# MCU-BLE.net
KiCad netlist of a schematic drawn in Altium Designer
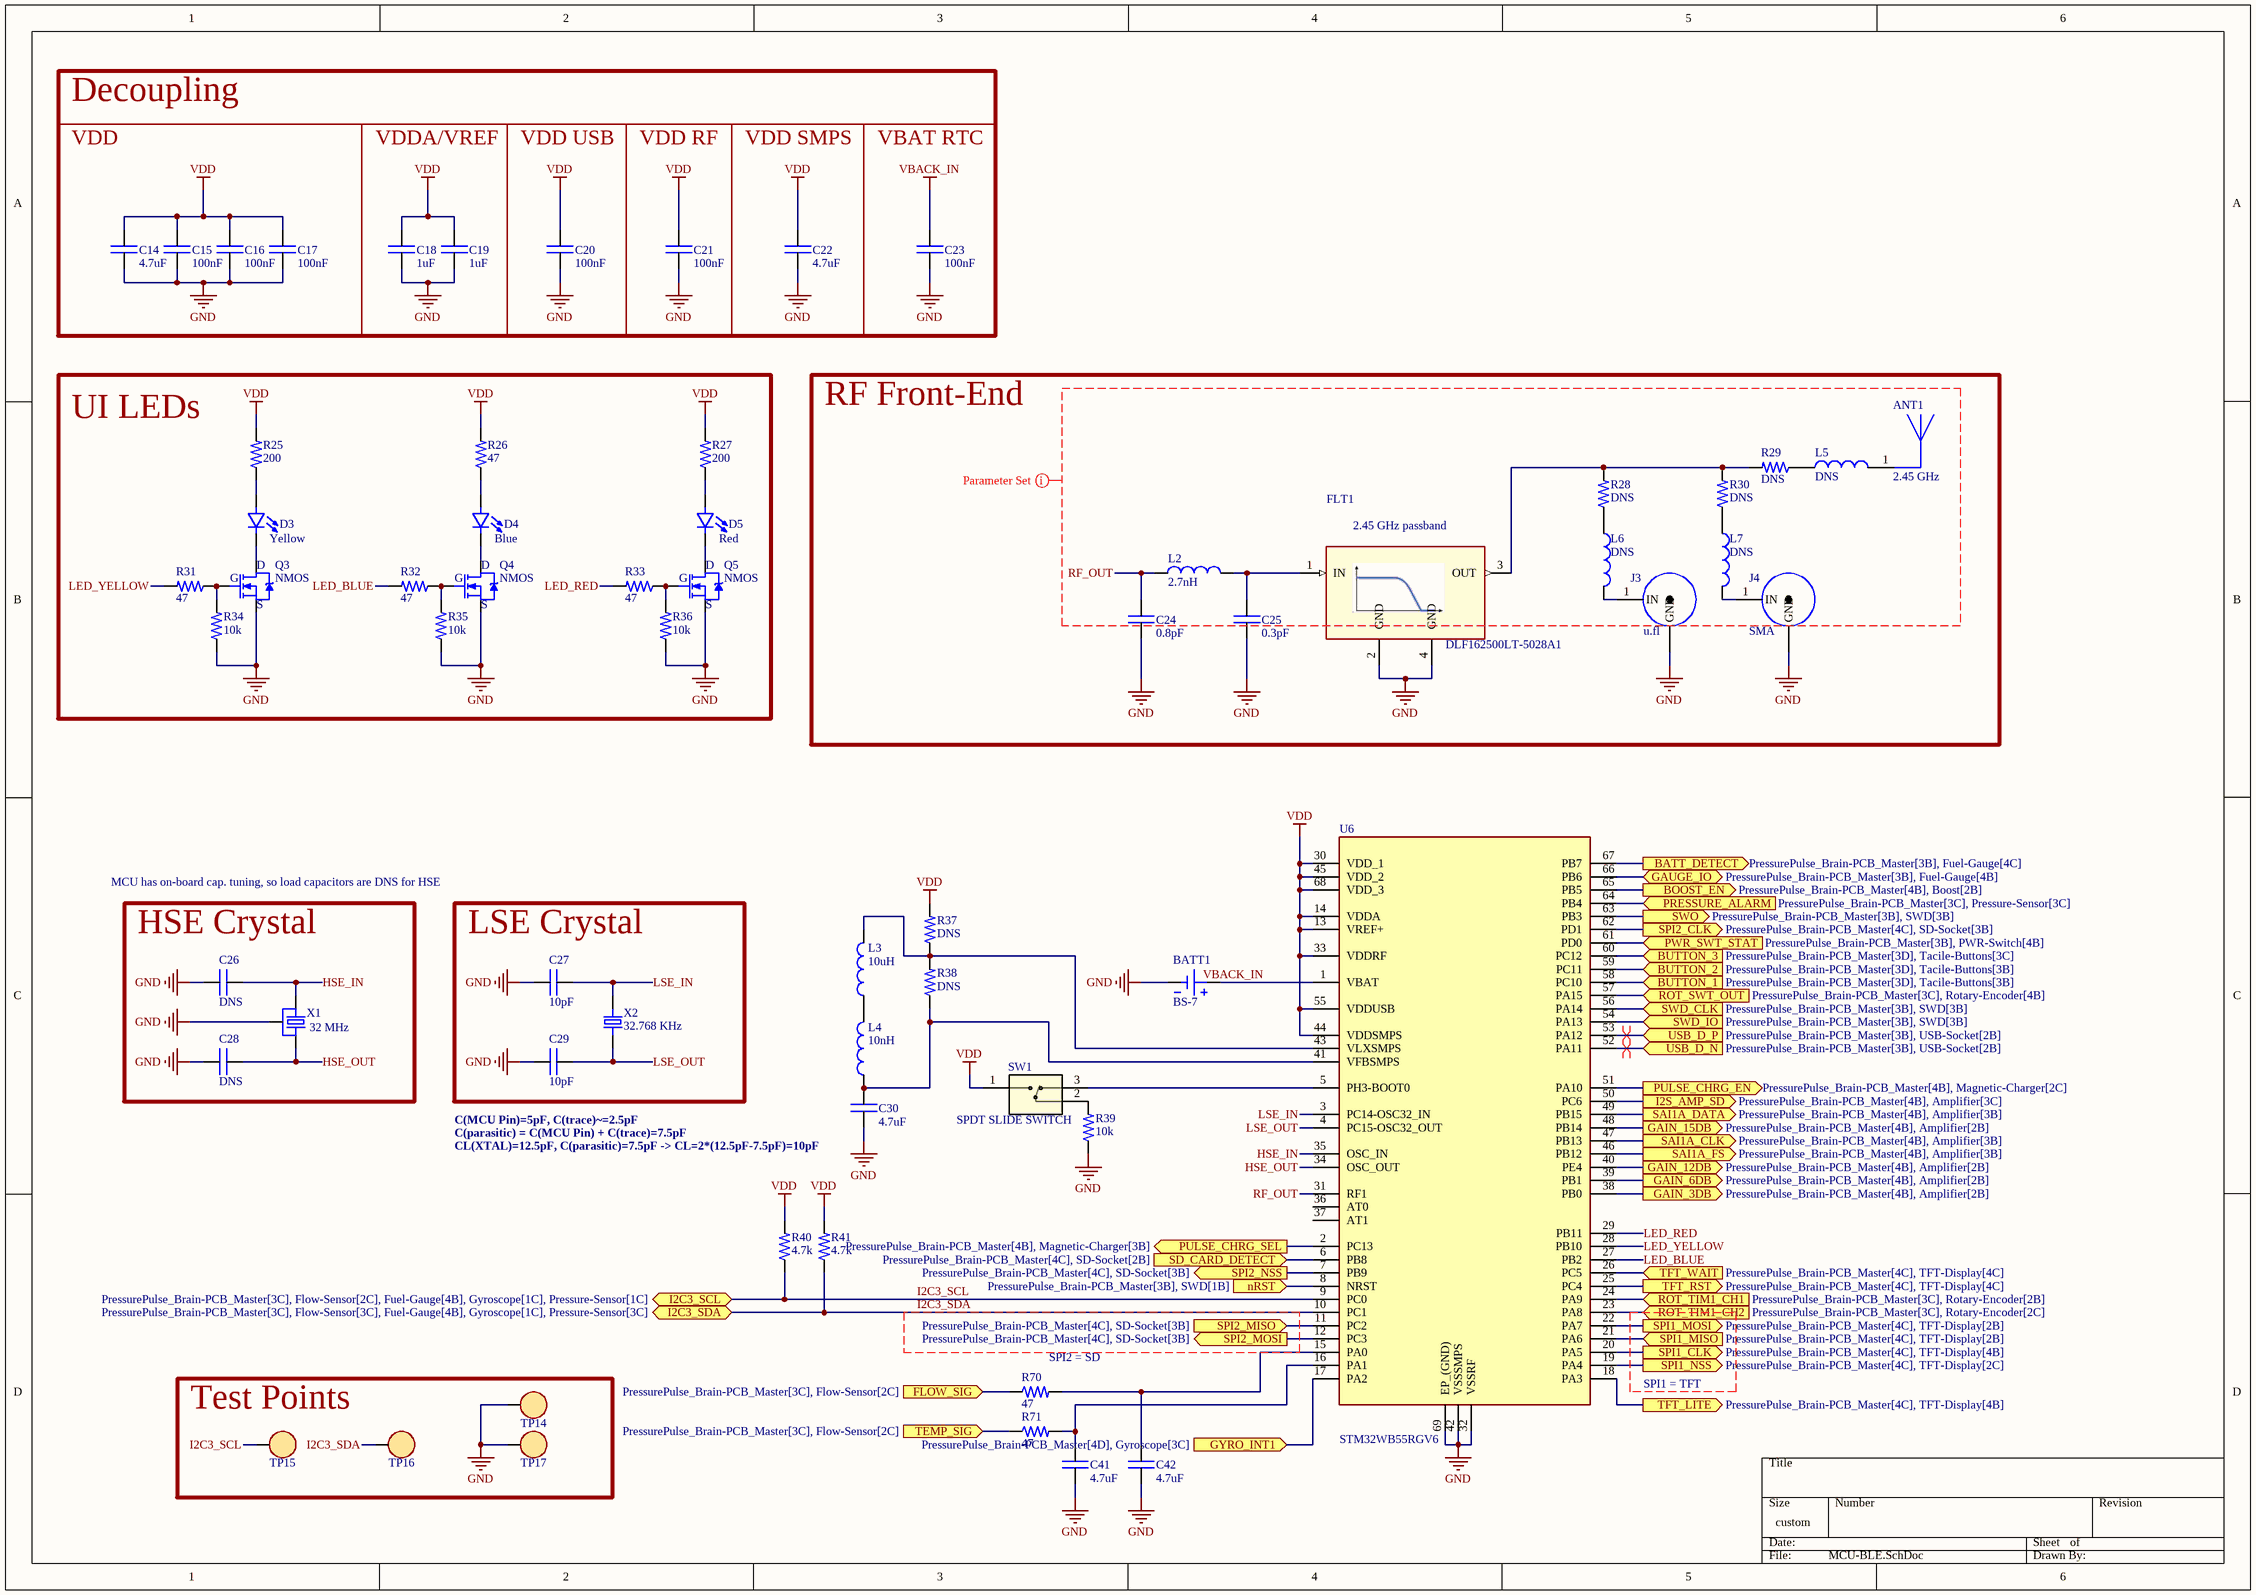
[diagram p0: MCU-BLE.SchDoc]

(export (version "E")
  (design (tool "Eeschema 10.0.6"))
  (components
    (comp (ref "ANT1")
      (value "CHIP ANTENNA")
      (footprint "PressurePulse:ANT_ANT7020LL05R0870A_PUL-L")
      (fields (field (name "MFR") "Pulse Electronics") (field (name "CENTER FREQUENCY") "2.45 GHz"))
      (libsource (lib "PressurePulse") (part "CHIP ANTENNA"))
    )
    (comp (ref "BATT1")
      (value "BS-7")
      (footprint "PressurePulse:BAT_BS-7")
      (description "Battery Holder (Open) Coin, 20.0mm 1 Cell PC Pin")
      (fields (field (name "MP") "BS-2-1") (field (name "MF") "Q&J"))
      (libsource (lib "PressurePulse") (part "COIN CELL BATT"))
    )
    (comp (ref "C14")
      (value "4.7uF")
      (footprint "PressurePulse:0402C")
      (description "Capaicitor")
      (fields (field (name "Comment") "CAP"))
      (libsource (lib "PressurePulse") (part "CAP"))
    )
    (comp (ref "C15")
      (value "100nF")
      (footprint "PressurePulse:0402C")
      (description "Capaicitor")
      (fields (field (name "Comment") "CAP"))
      (libsource (lib "PressurePulse") (part "CAP"))
    )
    (comp (ref "C16")
      (value "100nF")
      (footprint "PressurePulse:0402C")
      (description "Capaicitor")
      (fields (field (name "Comment") "CAP"))
      (libsource (lib "PressurePulse") (part "CAP"))
    )
    (comp (ref "C17")
      (value "100nF")
      (footprint "PressurePulse:0402C")
      (description "Capaicitor")
      (fields (field (name "Comment") "CAP"))
      (libsource (lib "PressurePulse") (part "CAP"))
    )
    (comp (ref "C18")
      (value "1uF")
      (footprint "PressurePulse:0402C")
      (description "Capaicitor")
      (fields (field (name "Comment") "CAP"))
      (libsource (lib "PressurePulse") (part "CAP"))
    )
    (comp (ref "C19")
      (value "1uF")
      (footprint "PressurePulse:0402C")
      (description "Capaicitor")
      (fields (field (name "Comment") "CAP"))
      (libsource (lib "PressurePulse") (part "CAP"))
    )
    (comp (ref "C20")
      (value "100nF")
      (footprint "PressurePulse:0402C")
      (description "Capaicitor")
      (fields (field (name "Comment") "CAP"))
      (libsource (lib "PressurePulse") (part "CAP"))
    )
    (comp (ref "C21")
      (value "100nF")
      (footprint "PressurePulse:0402C")
      (description "Capaicitor")
      (fields (field (name "Comment") "CAP"))
      (libsource (lib "PressurePulse") (part "CAP"))
    )
    (comp (ref "C22")
      (value "4.7uF")
      (footprint "PressurePulse:0402C")
      (description "Capaicitor")
      (fields (field (name "Comment") "CAP"))
      (libsource (lib "PressurePulse") (part "CAP"))
    )
    (comp (ref "C23")
      (value "100nF")
      (footprint "PressurePulse:0402C")
      (description "Capaicitor")
      (fields (field (name "Comment") "CAP"))
      (libsource (lib "PressurePulse") (part "CAP"))
    )
    (comp (ref "C24")
      (value "0.8pF")
      (footprint "PressurePulse:0603C")
      (description "Capacitor")
      (fields (field (name "Comment") "CAP"))
      (libsource (lib "PressurePulse") (part "CAP"))
    )
    (comp (ref "C25")
      (value "0.3pF")
      (footprint "PressurePulse:0402C")
      (description "Capacitor")
      (fields (field (name "Comment") "CAP"))
      (libsource (lib "PressurePulse") (part "CAP"))
    )
    (comp (ref "C26")
      (value "DNS")
      (footprint "PressurePulse:0402C")
      (description "Capaicitor")
      (fields (field (name "Comment") "CAP"))
      (libsource (lib "PressurePulse") (part "CAP"))
    )
    (comp (ref "C27")
      (value "10pF")
      (footprint "PressurePulse:0402C")
      (description "Capaicitor")
      (fields (field (name "Comment") "CAP"))
      (libsource (lib "PressurePulse") (part "CAP"))
    )
    (comp (ref "C28")
      (value "DNS")
      (footprint "PressurePulse:0402C")
      (description "Capaicitor")
      (fields (field (name "Comment") "CAP"))
      (libsource (lib "PressurePulse") (part "CAP"))
    )
    (comp (ref "C29")
      (value "10pF")
      (footprint "PressurePulse:0402C")
      (description "Capaicitor")
      (fields (field (name "Comment") "CAP"))
      (libsource (lib "PressurePulse") (part "CAP"))
    )
    (comp (ref "C30")
      (value "4.7uF")
      (footprint "PressurePulse:0402C")
      (description "Capaicitor")
      (fields (field (name "Comment") "CAP"))
      (libsource (lib "PressurePulse") (part "CAP"))
    )
    (comp (ref "C41")
      (value "4.7uF")
      (footprint "PressurePulse:0402C")
      (description "Capacitor")
      (fields (field (name "Comment") "CAP"))
      (libsource (lib "PressurePulse") (part "CAP"))
    )
    (comp (ref "C42")
      (value "4.7uF")
      (footprint "PressurePulse:0402C")
      (description "Capacitor")
      (fields (field (name "Comment") "CAP"))
      (libsource (lib "PressurePulse") (part "CAP"))
    )
    (comp (ref "D3")
      (value "LED - single")
      (footprint "PressurePulse:0603-LED")
      (description "LED")
      (fields (field (name "COLOR") "Yellow"))
      (libsource (lib "PressurePulse") (part "LED - single"))
    )
    (comp (ref "D4")
      (value "LED - single")
      (footprint "PressurePulse:0603-LED")
      (description "LED")
      (fields (field (name "COLOR") "Blue"))
      (libsource (lib "PressurePulse") (part "LED - single"))
    )
    (comp (ref "D5")
      (value "LED - single")
      (footprint "PressurePulse:0603-LED")
      (description "LED")
      (fields (field (name "COLOR") "Red"))
      (libsource (lib "PressurePulse") (part "LED - single"))
    )
    (comp (ref "FLT1")
      (value "DLF162500LT-5028A1")
      (footprint "PressurePulse:DLF-4_1P6X0P8")
      (description "RF FILTER LOW PASS 2.45GHZ 0603")
      (fields (field (name "MFR") "TDK"))
      (libsource (lib "PressurePulse") (part "2.45GHz LPF"))
    )
    (comp (ref "J3")
      (value "u.fl")
      (footprint "PressurePulse:U.FL")
      (description "u.fl 50Ohm")
      (fields (field (name "MFR") "HRS(Hirose)"))
      (libsource (lib "PressurePulse") (part "u.fl CONN"))
    )
    (comp (ref "J4")
      (value "SMA")
      (footprint "PressurePulse:SMA TH RA")
      (description "SMA 50Ohm")
      (fields (field (name "MFR") "DreamLNK"))
      (libsource (lib "PressurePulse") (part "SMA"))
    )
    (comp (ref "L2")
      (value "2.7nH")
      (footprint "PressurePulse:0402L")
      (description "INDUCTOR")
      (fields (field (name "Comment") "IND"))
      (libsource (lib "PressurePulse") (part "IND"))
    )
    (comp (ref "L3")
      (value "10uH")
      (footprint "PressurePulse:0805L")
      (description "INDUCTOR")
      (fields (field (name "Comment") "IND"))
      (libsource (lib "PressurePulse") (part "IND"))
    )
    (comp (ref "L4")
      (value "10nH")
      (footprint "PressurePulse:0402L")
      (description "INDUCTOR")
      (fields (field (name "Comment") "IND"))
      (libsource (lib "PressurePulse") (part "IND"))
    )
    (comp (ref "L5")
      (value "DNS")
      (footprint "PressurePulse:0402L")
      (description "INDUCTOR")
      (fields (field (name "Comment") "IND"))
      (libsource (lib "PressurePulse") (part "IND"))
    )
    (comp (ref "L6")
      (value "DNS")
      (footprint "PressurePulse:0402L")
      (description "INDUCTOR")
      (fields (field (name "Comment") "IND"))
      (libsource (lib "PressurePulse") (part "IND"))
    )
    (comp (ref "L7")
      (value "DNS")
      (footprint "PressurePulse:0402L")
      (description "INDUCTOR")
      (fields (field (name "Comment") "IND"))
      (libsource (lib "PressurePulse") (part "IND"))
    )
    (comp (ref "Q3")
      (value "NMOS")
      (footprint "PressurePulse:SOT-23")
      (description "100V 1.6A 1.3W 220mΩ@10V,1.6A N Channel SOT-23  MOSFETs ROHS")
      (fields (field (name "MFR") "Infineon"))
      (libsource (lib "PressurePulse") (part "NMOS"))
    )
    (comp (ref "Q4")
      (value "NMOS")
      (footprint "PressurePulse:SOT-23")
      (description "100V 1.6A 1.3W 220mΩ@10V,1.6A N Channel SOT-23  MOSFETs ROHS")
      (fields (field (name "MFR") "Infineon"))
      (libsource (lib "PressurePulse") (part "NMOS"))
    )
    (comp (ref "Q5")
      (value "NMOS")
      (footprint "PressurePulse:SOT-23")
      (description "100V 1.6A 1.3W 220mΩ@10V,1.6A N Channel SOT-23  MOSFETs ROHS")
      (fields (field (name "MFR") "Infineon"))
      (libsource (lib "PressurePulse") (part "NMOS"))
    )
    (comp (ref "R25")
      (value "200")
      (footprint "PressurePulse:0402R")
      (description "Resistor")
      (fields (field (name "Comment") "RES"))
      (libsource (lib "PressurePulse") (part "RES"))
    )
    (comp (ref "R26")
      (value "47")
      (footprint "PressurePulse:0402R")
      (description "Resistor")
      (fields (field (name "Comment") "RES"))
      (libsource (lib "PressurePulse") (part "RES"))
    )
    (comp (ref "R27")
      (value "200")
      (footprint "PressurePulse:0402R")
      (description "Resistor")
      (fields (field (name "Comment") "RES"))
      (libsource (lib "PressurePulse") (part "RES"))
    )
    (comp (ref "R28")
      (value "DNS")
      (footprint "PressurePulse:0402R")
      (description "Resistor")
      (fields (field (name "Comment") "RES"))
      (libsource (lib "PressurePulse") (part "RES"))
    )
    (comp (ref "R29")
      (value "DNS")
      (footprint "PressurePulse:0402R")
      (description "Resistor")
      (fields (field (name "Comment") "RES"))
      (libsource (lib "PressurePulse") (part "RES"))
    )
    (comp (ref "R30")
      (value "DNS")
      (footprint "PressurePulse:0402R")
      (description "Resistor")
      (fields (field (name "Comment") "RES"))
      (libsource (lib "PressurePulse") (part "RES"))
    )
    (comp (ref "R31")
      (value "47")
      (footprint "PressurePulse:0402R")
      (description "Resistor")
      (fields (field (name "Comment") "RES"))
      (libsource (lib "PressurePulse") (part "RES"))
    )
    (comp (ref "R32")
      (value "47")
      (footprint "PressurePulse:0402R")
      (description "Resistor")
      (fields (field (name "Comment") "RES"))
      (libsource (lib "PressurePulse") (part "RES"))
    )
    (comp (ref "R33")
      (value "47")
      (footprint "PressurePulse:0402R")
      (description "Resistor")
      (fields (field (name "Comment") "RES"))
      (libsource (lib "PressurePulse") (part "RES"))
    )
    (comp (ref "R34")
      (value "10k")
      (footprint "PressurePulse:0402R")
      (description "Resistor")
      (fields (field (name "Comment") "RES"))
      (libsource (lib "PressurePulse") (part "RES"))
    )
    (comp (ref "R35")
      (value "10k")
      (footprint "PressurePulse:0402R")
      (description "Resistor")
      (fields (field (name "Comment") "RES"))
      (libsource (lib "PressurePulse") (part "RES"))
    )
    (comp (ref "R36")
      (value "10k")
      (footprint "PressurePulse:0402R")
      (description "Resistor")
      (fields (field (name "Comment") "RES"))
      (libsource (lib "PressurePulse") (part "RES"))
    )
    (comp (ref "R37")
      (value "DNS")
      (footprint "PressurePulse:0402R")
      (description "Resistor")
      (fields (field (name "Comment") "RES"))
      (libsource (lib "PressurePulse") (part "RES"))
    )
    (comp (ref "R38")
      (value "DNS")
      (footprint "PressurePulse:0402R")
      (description "Resistor")
      (fields (field (name "Comment") "RES"))
      (libsource (lib "PressurePulse") (part "RES"))
    )
    (comp (ref "R39")
      (value "10k")
      (footprint "PressurePulse:0402R")
      (description "Resistor")
      (fields (field (name "Comment") "RES"))
      (libsource (lib "PressurePulse") (part "RES"))
    )
    (comp (ref "R40")
      (value "4.7k")
      (footprint "PressurePulse:0402R")
      (description "Resistor")
      (fields (field (name "Comment") "RES"))
      (libsource (lib "PressurePulse") (part "RES"))
    )
    (comp (ref "R41")
      (value "4.7k")
      (footprint "PressurePulse:0402R")
      (description "Resistor")
      (fields (field (name "Comment") "RES"))
      (libsource (lib "PressurePulse") (part "RES"))
    )
    (comp (ref "R70")
      (value "47")
      (footprint "PressurePulse:0402R")
      (description "Resistor")
      (fields (field (name "Comment") "RES"))
      (libsource (lib "PressurePulse") (part "RES"))
    )
    (comp (ref "R71")
      (value "47")
      (footprint "PressurePulse:0402R")
      (description "Resistor")
      (fields (field (name "Comment") "RES"))
      (libsource (lib "PressurePulse") (part "RES"))
    )
    (comp (ref "SW1")
      (value "SPDT SLIDE SWITCH")
      (footprint "PressurePulse:JS102011SCQN")
      (fields (field (name "MFR") "C&K"))
      (libsource (lib "PressurePulse") (part "SPDT SLIDE SWITCH"))
    )
    (comp (ref "TP14")
      (value "RH-5019")
      (footprint "PressurePulse:TP - RH-5019")
      (fields (field (name "MFR") "ronghe"))
      (libsource (lib "PressurePulse") (part "TEST POINT"))
    )
    (comp (ref "TP15")
      (value "RH-5019")
      (footprint "PressurePulse:TP - RH-5019")
      (fields (field (name "MFR") "ronghe"))
      (libsource (lib "PressurePulse") (part "TEST POINT"))
    )
    (comp (ref "TP16")
      (value "RH-5019")
      (footprint "PressurePulse:TP - RH-5019")
      (fields (field (name "MFR") "ronghe"))
      (libsource (lib "PressurePulse") (part "TEST POINT"))
    )
    (comp (ref "TP17")
      (value "RH-5019")
      (footprint "PressurePulse:TP - RH-5019")
      (fields (field (name "MFR") "ronghe"))
      (libsource (lib "PressurePulse") (part "TEST POINT"))
    )
    (comp (ref "U6")
      (value "STM32WB55RGV6")
      (footprint "PressurePulse:VQFN-68")
      (fields (field (name "MFR") "STMicroelectronics"))
      (libsource (lib "PressurePulse") (part "STM32WB55RGV6"))
    )
    (comp (ref "X1")
      (value "XTAL-OSC_32MHz")
      (footprint "PressurePulse:32MHZ_SMD1612-4P")
      (description "SMD Tuning Fork Crystal")
      (fields (field (name "FREQUENCY") "32 MHz"))
      (libsource (lib "PressurePulse") (part "XTAL-OSC_32MHz"))
    )
    (comp (ref "X2")
      (value "XTAL-OSC_32.768kHz")
      (footprint "PressurePulse:XTAL_ECS-.327-12.5-34B-TR")
      (description "32.768kHz 12.5pF ±20ppm SMD3215-2P  Crystals ROHS")
      (fields (field (name "MFR") "CITIZEN") (field (name "FREQUENCY") "32.768 KHz"))
      (libsource (lib "PressurePulse") (part "XTAL-OSC_32.768kHz"))
    )
  )
  (nets
    (net (code "1") (name "/BATT_DETECT") (class "Default")
      (node (ref "U6") (pin "67") (pinfunction "PB7_67") (pintype "passive"))
    )
    (net (code "2") (name "/BOOST_EN") (class "Default")
      (node (ref "U6") (pin "65") (pinfunction "PB5_65") (pintype "passive"))
    )
    (net (code "3") (name "/BUTTON_1") (class "Default")
      (node (ref "U6") (pin "58") (pinfunction "PC10_58") (pintype "passive"))
    )
    (net (code "4") (name "/BUTTON_2") (class "Default")
      (node (ref "U6") (pin "59") (pinfunction "PC11_59") (pintype "passive"))
    )
    (net (code "5") (name "/BUTTON_3") (class "Default")
      (node (ref "U6") (pin "60") (pinfunction "PC12_60") (pintype "passive"))
    )
    (net (code "6") (name "/FLOW_SIG") (class "Default")
      (node (ref "R70") (pin "1") (pinfunction "1_1") (pintype "passive"))
    )
    (net (code "7") (name "/GAIN_3DB") (class "Default")
      (node (ref "U6") (pin "38") (pinfunction "PB0_38") (pintype "passive"))
    )
    (net (code "8") (name "/GAIN_6DB") (class "Default")
      (node (ref "U6") (pin "39") (pinfunction "PB1_39") (pintype "passive"))
    )
    (net (code "9") (name "/GAIN_12DB") (class "Default")
      (node (ref "U6") (pin "40") (pinfunction "PE4_40") (pintype "passive"))
    )
    (net (code "10") (name "/GAIN_15DB") (class "Default")
      (node (ref "U6") (pin "48") (pinfunction "PB14_48") (pintype "passive"))
    )
    (net (code "11") (name "/GAUGE_IO") (class "Default")
      (node (ref "U6") (pin "66") (pinfunction "PB6_66") (pintype "passive"))
    )
    (net (code "12") (name "/GYRO_INT1") (class "Default")
      (node (ref "U6") (pin "17") (pinfunction "PA2_17") (pintype "passive"))
    )
    (net (code "13") (name "/HSE_IN") (class "Default")
      (node (ref "C26") (pin "1") (pinfunction "1_1") (pintype "passive"))
      (node (ref "U6") (pin "35") (pinfunction "OSC_IN_35") (pintype "passive"))
      (node (ref "X1") (pin "1") (pinfunction "1_1") (pintype "passive"))
    )
    (net (code "14") (name "/HSE_OUT") (class "Default")
      (node (ref "C28") (pin "1") (pinfunction "1_1") (pintype "passive"))
      (node (ref "U6") (pin "34") (pinfunction "OSC_OUT_34") (pintype "passive"))
      (node (ref "X1") (pin "3") (pinfunction "3_3") (pintype "passive"))
    )
    (net (code "15") (name "/I2C3_SCL") (class "Default")
      (node (ref "R40") (pin "1") (pinfunction "1_1") (pintype "passive"))
      (node (ref "TP15") (pin "1") (pinfunction "1_1") (pintype "passive"))
      (node (ref "U6") (pin "9") (pinfunction "PC0_9") (pintype "passive"))
    )
    (net (code "16") (name "/I2C3_SDA") (class "Default")
      (node (ref "R41") (pin "1") (pinfunction "1_1") (pintype "passive"))
      (node (ref "TP16") (pin "1") (pinfunction "1_1") (pintype "passive"))
      (node (ref "U6") (pin "10") (pinfunction "PC1_10") (pintype "passive"))
    )
    (net (code "17") (name "/I2S_AMP_SD") (class "Default")
      (node (ref "U6") (pin "50") (pinfunction "PC6_50") (pintype "passive"))
    )
    (net (code "18") (name "/LED_BLUE") (class "Default")
      (node (ref "R32") (pin "2") (pinfunction "2_2") (pintype "passive"))
      (node (ref "U6") (pin "27") (pinfunction "PB2_27") (pintype "passive"))
    )
    (net (code "19") (name "/LED_RED") (class "Default")
      (node (ref "R33") (pin "2") (pinfunction "2_2") (pintype "passive"))
      (node (ref "U6") (pin "29") (pinfunction "PB11_29") (pintype "passive"))
    )
    (net (code "20") (name "/LED_YELLOW") (class "Default")
      (node (ref "R31") (pin "2") (pinfunction "2_2") (pintype "passive"))
      (node (ref "U6") (pin "28") (pinfunction "PB10_28") (pintype "passive"))
    )
    (net (code "21") (name "/LSE_IN") (class "Default")
      (node (ref "C27") (pin "1") (pinfunction "1_1") (pintype "passive"))
      (node (ref "U6") (pin "3") (pinfunction "PC14-OSC32_IN_3") (pintype "passive"))
      (node (ref "X2") (pin "2") (pinfunction "2_2") (pintype "passive"))
    )
    (net (code "22") (name "/LSE_OUT") (class "Default")
      (node (ref "C29") (pin "1") (pinfunction "1_1") (pintype "passive"))
      (node (ref "U6") (pin "4") (pinfunction "PC15-OSC32_OUT_4") (pintype "passive"))
      (node (ref "X2") (pin "1") (pinfunction "1_1") (pintype "passive"))
    )
    (net (code "23") (name "/PRESSURE_ALARM") (class "Default")
      (node (ref "U6") (pin "64") (pinfunction "PB4_64") (pintype "passive"))
    )
    (net (code "24") (name "/PULSE_CHRG_EN") (class "Default")
      (node (ref "U6") (pin "51") (pinfunction "PA10_51") (pintype "passive"))
    )
    (net (code "25") (name "/PULSE_CHRG_SEL") (class "Default")
      (node (ref "U6") (pin "2") (pinfunction "PC13_2") (pintype "passive"))
    )
    (net (code "26") (name "/PWR_SWT_STAT") (class "Default")
      (node (ref "U6") (pin "61") (pinfunction "PD0_61") (pintype "passive"))
    )
    (net (code "27") (name "/RF_OUT") (class "Default")
      (node (ref "C24") (pin "2") (pinfunction "2_2") (pintype "passive"))
      (node (ref "L2") (pin "1") (pinfunction "1_1") (pintype "passive"))
      (node (ref "U6") (pin "31") (pinfunction "RF1_31") (pintype "passive"))
    )
    (net (code "28") (name "/ROT_SWT_OUT") (class "Default")
      (node (ref "U6") (pin "57") (pinfunction "PA15_57") (pintype "passive"))
    )
    (net (code "29") (name "/ROT_TIM1_CH1") (class "Default")
      (node (ref "U6") (pin "24") (pinfunction "PA9_24") (pintype "passive"))
    )
    (net (code "30") (name "/ROT_TIM1_CH2") (class "Default")
      (node (ref "U6") (pin "23") (pinfunction "PA8_23") (pintype "passive"))
    )
    (net (code "31") (name "/SAI1A_CLK") (class "Default")
      (node (ref "U6") (pin "47") (pinfunction "PB13_47") (pintype "passive"))
    )
    (net (code "32") (name "/SAI1A_DATA") (class "Default")
      (node (ref "U6") (pin "49") (pinfunction "PB15_49") (pintype "passive"))
    )
    (net (code "33") (name "/SAI1A_FS") (class "Default")
      (node (ref "U6") (pin "46") (pinfunction "PB12_46") (pintype "passive"))
    )
    (net (code "34") (name "/SD_CARD_DETECT") (class "Default")
      (node (ref "U6") (pin "6") (pinfunction "PB8_6") (pintype "passive"))
    )
    (net (code "35") (name "/SPI1_CLK") (class "Default")
      (node (ref "U6") (pin "20") (pinfunction "PA5_20") (pintype "passive"))
    )
    (net (code "36") (name "/SPI1_MISO") (class "Default")
      (node (ref "U6") (pin "21") (pinfunction "PA6_21") (pintype "passive"))
    )
    (net (code "37") (name "/SPI1_MOSI") (class "Default")
      (node (ref "U6") (pin "22") (pinfunction "PA7_22") (pintype "passive"))
    )
    (net (code "38") (name "/SPI1_NSS") (class "Default")
      (node (ref "U6") (pin "19") (pinfunction "PA4_19") (pintype "passive"))
    )
    (net (code "39") (name "/SPI2_CLK") (class "Default")
      (node (ref "U6") (pin "62") (pinfunction "PD1_62") (pintype "passive"))
    )
    (net (code "40") (name "/SPI2_MISO") (class "Default")
      (node (ref "U6") (pin "11") (pinfunction "PC2_11") (pintype "passive"))
    )
    (net (code "41") (name "/SPI2_MOSI") (class "Default")
      (node (ref "U6") (pin "12") (pinfunction "PC3_12") (pintype "passive"))
    )
    (net (code "42") (name "/SPI2_NSS") (class "Default")
      (node (ref "U6") (pin "7") (pinfunction "PB9_7") (pintype "passive"))
    )
    (net (code "43") (name "/SWD_CLK") (class "Default")
      (node (ref "U6") (pin "56") (pinfunction "PA14_56") (pintype "passive"))
    )
    (net (code "44") (name "/SWD_IO") (class "Default")
      (node (ref "U6") (pin "54") (pinfunction "PA13_54") (pintype "passive"))
    )
    (net (code "45") (name "/SWO") (class "Default")
      (node (ref "U6") (pin "63") (pinfunction "PB3_63") (pintype "passive"))
    )
    (net (code "46") (name "/TEMP_SIG") (class "Default")
      (node (ref "R71") (pin "1") (pinfunction "1_1") (pintype "passive"))
    )
    (net (code "47") (name "/TFT_LITE") (class "Default")
      (node (ref "U6") (pin "18") (pinfunction "PA3_18") (pintype "passive"))
    )
    (net (code "48") (name "/TFT_RST") (class "Default")
      (node (ref "U6") (pin "25") (pinfunction "PC4_25") (pintype "passive"))
    )
    (net (code "49") (name "/TFT_WAIT") (class "Default")
      (node (ref "U6") (pin "26") (pinfunction "PC5_26") (pintype "passive"))
    )
    (net (code "50") (name "/USB_D_N") (class "Default")
      (node (ref "U6") (pin "52") (pinfunction "PA11_52") (pintype "passive"))
    )
    (net (code "51") (name "/USB_D_P") (class "Default")
      (node (ref "U6") (pin "53") (pinfunction "PA12_53") (pintype "passive"))
    )
    (net (code "52") (name "/nRST") (class "Default")
      (node (ref "U6") (pin "8") (pinfunction "NRST_8") (pintype "passive"))
    )
    (net (code "53") (name "GND") (class "Default")
      (node (ref "BATT1") (pin "2") (pinfunction "NEG_2") (pintype "passive"))
      (node (ref "C14") (pin "1") (pinfunction "1_1") (pintype "passive"))
      (node (ref "C15") (pin "1") (pinfunction "1_1") (pintype "passive"))
      (node (ref "C16") (pin "1") (pinfunction "1_1") (pintype "passive"))
      (node (ref "C17") (pin "1") (pinfunction "1_1") (pintype "passive"))
      (node (ref "C18") (pin "1") (pinfunction "1_1") (pintype "passive"))
      (node (ref "C19") (pin "1") (pinfunction "1_1") (pintype "passive"))
      (node (ref "C20") (pin "1") (pinfunction "1_1") (pintype "passive"))
      (node (ref "C21") (pin "1") (pinfunction "1_1") (pintype "passive"))
      (node (ref "C22") (pin "1") (pinfunction "1_1") (pintype "passive"))
      (node (ref "C23") (pin "1") (pinfunction "1_1") (pintype "passive"))
      (node (ref "C24") (pin "1") (pinfunction "1_1") (pintype "passive"))
      (node (ref "C25") (pin "1") (pinfunction "1_1") (pintype "passive"))
      (node (ref "C26") (pin "2") (pinfunction "2_2") (pintype "passive"))
      (node (ref "C27") (pin "2") (pinfunction "2_2") (pintype "passive"))
      (node (ref "C28") (pin "2") (pinfunction "2_2") (pintype "passive"))
      (node (ref "C29") (pin "2") (pinfunction "2_2") (pintype "passive"))
      (node (ref "C30") (pin "1") (pinfunction "1_1") (pintype "passive"))
      (node (ref "C41") (pin "1") (pinfunction "1_1") (pintype "passive"))
      (node (ref "C42") (pin "1") (pinfunction "1_1") (pintype "passive"))
      (node (ref "FLT1") (pin "2") (pinfunction "GND_2") (pintype "power_in"))
      (node (ref "FLT1") (pin "4") (pinfunction "GND_4") (pintype "power_in"))
      (node (ref "J3") (pin "GND") (pinfunction "GND_GND") (pintype "passive"))
      (node (ref "J4") (pin "GND") (pinfunction "GND_GND") (pintype "passive"))
      (node (ref "Q3") (pin "S") (pinfunction "S_S") (pintype "passive"))
      (node (ref "Q4") (pin "S") (pinfunction "S_S") (pintype "passive"))
      (node (ref "Q5") (pin "S") (pinfunction "S_S") (pintype "passive"))
      (node (ref "R34") (pin "1") (pinfunction "1_1") (pintype "passive"))
      (node (ref "R35") (pin "1") (pinfunction "1_1") (pintype "passive"))
      (node (ref "R36") (pin "1") (pinfunction "1_1") (pintype "passive"))
      (node (ref "R39") (pin "1") (pinfunction "1_1") (pintype "passive"))
      (node (ref "TP14") (pin "1") (pinfunction "1_1") (pintype "passive"))
      (node (ref "TP17") (pin "1") (pinfunction "1_1") (pintype "passive"))
      (node (ref "U6") (pin "32") (pinfunction "VSSRF_32") (pintype "passive"))
      (node (ref "U6") (pin "42") (pinfunction "VSSSMPS_42") (pintype "passive"))
      (node (ref "U6") (pin "69") (pinfunction "EP_(GND)_69") (pintype "passive"))
      (node (ref "X1") (pin "GND") (pinfunction "GND_GND") (pintype "passive"))
    )
    (net (code "54") (name "Net-(ANT1-Pad1)") (class "Default")
      (node (ref "ANT1") (pin "1") (pinfunction "1_1") (pintype "passive"))
      (node (ref "L5") (pin "2") (pinfunction "2_2") (pintype "passive"))
    )
    (net (code "55") (name "Net-(D3-A)") (class "Default")
      (node (ref "D3") (pin "1") (pinfunction "A_1") (pintype "passive"))
      (node (ref "R25") (pin "1") (pinfunction "1_1") (pintype "passive"))
    )
    (net (code "56") (name "Net-(D3-C)") (class "Default")
      (node (ref "D3") (pin "2") (pinfunction "C_2") (pintype "passive"))
      (node (ref "Q3") (pin "D") (pinfunction "D_D") (pintype "passive"))
    )
    (net (code "57") (name "Net-(D4-A)") (class "Default")
      (node (ref "D4") (pin "1") (pinfunction "A_1") (pintype "passive"))
      (node (ref "R26") (pin "1") (pinfunction "1_1") (pintype "passive"))
    )
    (net (code "58") (name "Net-(D4-C)") (class "Default")
      (node (ref "D4") (pin "2") (pinfunction "C_2") (pintype "passive"))
      (node (ref "Q4") (pin "D") (pinfunction "D_D") (pintype "passive"))
    )
    (net (code "59") (name "Net-(D5-A)") (class "Default")
      (node (ref "D5") (pin "1") (pinfunction "A_1") (pintype "passive"))
      (node (ref "R27") (pin "1") (pinfunction "1_1") (pintype "passive"))
    )
    (net (code "60") (name "Net-(D5-C)") (class "Default")
      (node (ref "D5") (pin "2") (pinfunction "C_2") (pintype "passive"))
      (node (ref "Q5") (pin "D") (pinfunction "D_D") (pintype "passive"))
    )
    (net (code "61") (name "Net-(FLT1-IN)") (class "Default")
      (node (ref "C25") (pin "2") (pinfunction "2_2") (pintype "passive"))
      (node (ref "FLT1") (pin "1") (pinfunction "IN_1") (pintype "input"))
      (node (ref "L2") (pin "2") (pinfunction "2_2") (pintype "passive"))
    )
    (net (code "62") (name "Net-(FLT1-OUT)") (class "Default")
      (node (ref "FLT1") (pin "3") (pinfunction "OUT_3") (pintype "output"))
      (node (ref "R28") (pin "2") (pinfunction "2_2") (pintype "passive"))
      (node (ref "R29") (pin "2") (pinfunction "2_2") (pintype "passive"))
      (node (ref "R30") (pin "2") (pinfunction "2_2") (pintype "passive"))
    )
    (net (code "63") (name "Net-(J3-IN)") (class "Default")
      (node (ref "J3") (pin "1") (pinfunction "IN_1") (pintype "passive"))
      (node (ref "L6") (pin "2") (pinfunction "2_2") (pintype "passive"))
    )
    (net (code "64") (name "Net-(J4-IN)") (class "Default")
      (node (ref "J4") (pin "1") (pinfunction "IN_1") (pintype "passive"))
      (node (ref "L7") (pin "2") (pinfunction "2_2") (pintype "passive"))
    )
    (net (code "65") (name "Net-(L3-Pad1)") (class "Default")
      (node (ref "L3") (pin "1") (pinfunction "1_1") (pintype "passive"))
      (node (ref "L4") (pin "2") (pinfunction "2_2") (pintype "passive"))
    )
    (net (code "66") (name "Net-(L5-Pad1)") (class "Default")
      (node (ref "L5") (pin "1") (pinfunction "1_1") (pintype "passive"))
      (node (ref "R29") (pin "1") (pinfunction "1_1") (pintype "passive"))
    )
    (net (code "67") (name "Net-(L6-Pad1)") (class "Default")
      (node (ref "L6") (pin "1") (pinfunction "1_1") (pintype "passive"))
      (node (ref "R28") (pin "1") (pinfunction "1_1") (pintype "passive"))
    )
    (net (code "68") (name "Net-(L7-Pad1)") (class "Default")
      (node (ref "L7") (pin "1") (pinfunction "1_1") (pintype "passive"))
      (node (ref "R30") (pin "1") (pinfunction "1_1") (pintype "passive"))
    )
    (net (code "69") (name "Net-(Q3-PadG)") (class "Default")
      (node (ref "Q3") (pin "G") (pinfunction "G_G") (pintype "passive"))
      (node (ref "R31") (pin "1") (pinfunction "1_1") (pintype "passive"))
      (node (ref "R34") (pin "2") (pinfunction "2_2") (pintype "passive"))
    )
    (net (code "70") (name "Net-(Q4-PadG)") (class "Default")
      (node (ref "Q4") (pin "G") (pinfunction "G_G") (pintype "passive"))
      (node (ref "R32") (pin "1") (pinfunction "1_1") (pintype "passive"))
      (node (ref "R35") (pin "2") (pinfunction "2_2") (pintype "passive"))
    )
    (net (code "71") (name "Net-(Q5-PadG)") (class "Default")
      (node (ref "Q5") (pin "G") (pinfunction "G_G") (pintype "passive"))
      (node (ref "R33") (pin "1") (pinfunction "1_1") (pintype "passive"))
      (node (ref "R36") (pin "2") (pinfunction "2_2") (pintype "passive"))
    )
    (net (code "72") (name "Net-(R39-Pad2)") (class "Default")
      (node (ref "R39") (pin "2") (pinfunction "2_2") (pintype "passive"))
      (node (ref "SW1") (pin "2") (pinfunction "2_2") (pintype "passive"))
    )
    (net (code "73") (name "Net-(U6-PA0)") (class "Default")
      (node (ref "C42") (pin "2") (pinfunction "2_2") (pintype "passive"))
      (node (ref "R70") (pin "2") (pinfunction "2_2") (pintype "passive"))
      (node (ref "U6") (pin "15") (pinfunction "PA0_15") (pintype "passive"))
    )
    (net (code "74") (name "Net-(U6-PA1)") (class "Default")
      (node (ref "C41") (pin "2") (pinfunction "2_2") (pintype "passive"))
      (node (ref "R71") (pin "2") (pinfunction "2_2") (pintype "passive"))
      (node (ref "U6") (pin "16") (pinfunction "PA1_16") (pintype "passive"))
    )
    (net (code "75") (name "Net-(U6-PH3-BOOT0)") (class "Default")
      (node (ref "SW1") (pin "3") (pinfunction "3_3") (pintype "passive"))
      (node (ref "U6") (pin "5") (pinfunction "PH3-BOOT0_5") (pintype "passive"))
    )
    (net (code "76") (name "Net-(U6-VFBSMPS)") (class "Default")
      (node (ref "C30") (pin "2") (pinfunction "2_2") (pintype "passive"))
      (node (ref "L4") (pin "1") (pinfunction "1_1") (pintype "passive"))
      (node (ref "R38") (pin "1") (pinfunction "1_1") (pintype "passive"))
      (node (ref "U6") (pin "41") (pinfunction "VFBSMPS_41") (pintype "passive"))
    )
    (net (code "77") (name "Net-(U6-VLXSMPS)") (class "Default")
      (node (ref "L3") (pin "2") (pinfunction "2_2") (pintype "passive"))
      (node (ref "R37") (pin "1") (pinfunction "1_1") (pintype "passive"))
      (node (ref "R38") (pin "2") (pinfunction "2_2") (pintype "passive"))
      (node (ref "U6") (pin "43") (pinfunction "VLXSMPS_43") (pintype "passive"))
    )
    (net (code "78") (name "VBACK_IN") (class "Default")
      (node (ref "BATT1") (pin "1") (pinfunction "POS_1") (pintype "passive"))
      (node (ref "C23") (pin "2") (pinfunction "2_2") (pintype "passive"))
      (node (ref "U6") (pin "1") (pinfunction "VBAT_1") (pintype "passive"))
    )
    (net (code "79") (name "VDD") (class "Default")
      (node (ref "C14") (pin "2") (pinfunction "2_2") (pintype "passive"))
      (node (ref "C15") (pin "2") (pinfunction "2_2") (pintype "passive"))
      (node (ref "C16") (pin "2") (pinfunction "2_2") (pintype "passive"))
      (node (ref "C17") (pin "2") (pinfunction "2_2") (pintype "passive"))
      (node (ref "C18") (pin "2") (pinfunction "2_2") (pintype "passive"))
      (node (ref "C19") (pin "2") (pinfunction "2_2") (pintype "passive"))
      (node (ref "C20") (pin "2") (pinfunction "2_2") (pintype "passive"))
      (node (ref "C21") (pin "2") (pinfunction "2_2") (pintype "passive"))
      (node (ref "C22") (pin "2") (pinfunction "2_2") (pintype "passive"))
      (node (ref "R25") (pin "2") (pinfunction "2_2") (pintype "passive"))
      (node (ref "R26") (pin "2") (pinfunction "2_2") (pintype "passive"))
      (node (ref "R27") (pin "2") (pinfunction "2_2") (pintype "passive"))
      (node (ref "R37") (pin "2") (pinfunction "2_2") (pintype "passive"))
      (node (ref "R40") (pin "2") (pinfunction "2_2") (pintype "passive"))
      (node (ref "R41") (pin "2") (pinfunction "2_2") (pintype "passive"))
      (node (ref "SW1") (pin "1") (pinfunction "1_1") (pintype "passive"))
      (node (ref "U6") (pin "13") (pinfunction "VREF+_13") (pintype "passive"))
      (node (ref "U6") (pin "14") (pinfunction "VDDA_14") (pintype "passive"))
      (node (ref "U6") (pin "30") (pinfunction "VDD_1_30") (pintype "passive"))
      (node (ref "U6") (pin "33") (pinfunction "VDDRF_33") (pintype "passive"))
      (node (ref "U6") (pin "44") (pinfunction "VDDSMPS_44") (pintype "passive"))
      (node (ref "U6") (pin "45") (pinfunction "VDD_2_45") (pintype "passive"))
      (node (ref "U6") (pin "55") (pinfunction "VDDUSB_55") (pintype "passive"))
      (node (ref "U6") (pin "68") (pinfunction "VDD_3_68") (pintype "passive"))
    )
    (net (code "80") (name "unconnected-(U6-AT0-Pad36)") (class "Default")
      (node (ref "U6") (pin "36") (pinfunction "AT0_36") (pintype "passive"))
    )
    (net (code "81") (name "unconnected-(U6-AT1-Pad37)") (class "Default")
      (node (ref "U6") (pin "37") (pinfunction "AT1_37") (pintype "passive"))
    )
  )
)
